# MCP41010.net
KiCad netlist of a schematic drawn in EasyEDA Pro
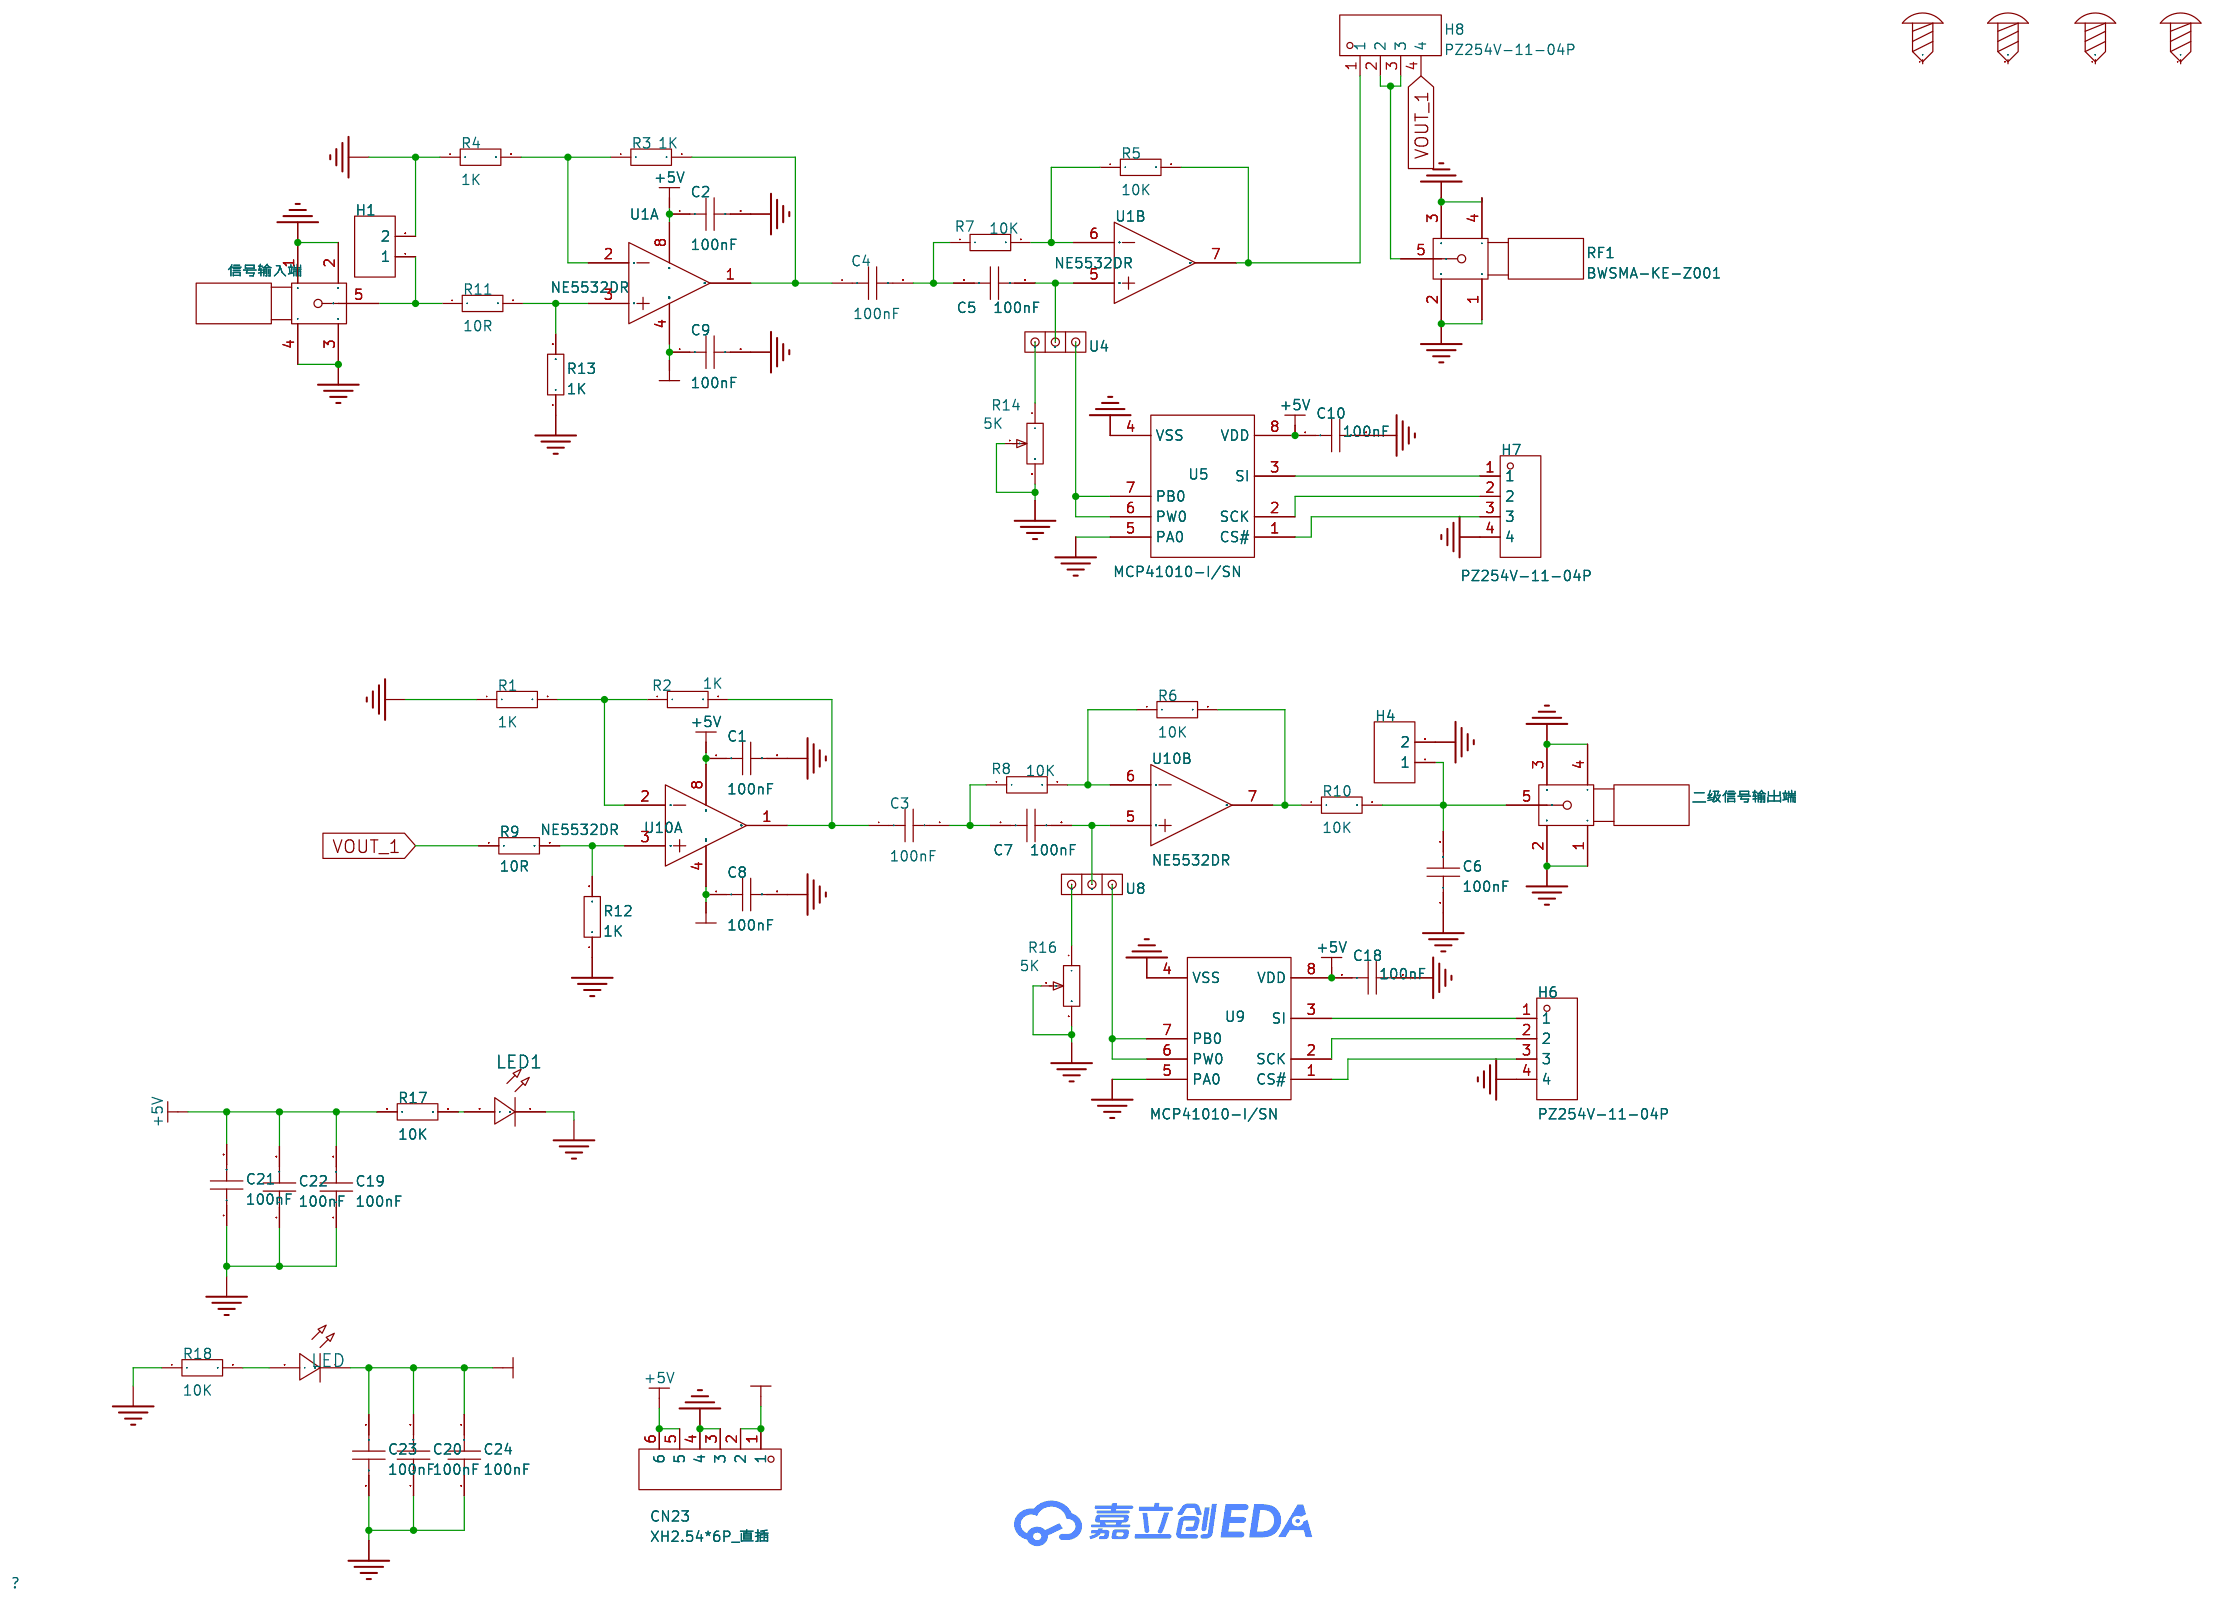
[diagram p0: schematic sheet]

(export (version "E")
  (design (tool "Eeschema 10.0.6"))
  (components
    (comp (ref "C1")
      (value "100nF")
      (footprint "easyedapro:C0805")
      (libsource (lib "easyedapro") (part "CapAcitance"))
    )
    (comp (ref "C2")
      (value "100nF")
      (footprint "easyedapro:C0805")
      (libsource (lib "easyedapro") (part "CapAcitance"))
    )
    (comp (ref "C3")
      (value "100nF")
      (footprint "easyedapro:C0805")
      (libsource (lib "easyedapro") (part "CapAcitance"))
    )
    (comp (ref "C4")
      (value "100nF")
      (footprint "easyedapro:C0805")
      (libsource (lib "easyedapro") (part "CapAcitance"))
    )
    (comp (ref "C5")
      (value "100nF")
      (footprint "easyedapro:C0805")
      (libsource (lib "easyedapro") (part "CapAcitance"))
    )
    (comp (ref "C6")
      (value "100nF")
      (footprint "easyedapro:C0805")
      (libsource (lib "easyedapro") (part "CapAcitance"))
    )
    (comp (ref "C7")
      (value "100nF")
      (footprint "easyedapro:C0805")
      (libsource (lib "easyedapro") (part "CapAcitance"))
    )
    (comp (ref "C8")
      (value "100nF")
      (footprint "easyedapro:C0805")
      (libsource (lib "easyedapro") (part "CapAcitance"))
    )
    (comp (ref "C9")
      (value "100nF")
      (footprint "easyedapro:C0805")
      (libsource (lib "easyedapro") (part "CapAcitance"))
    )
    (comp (ref "C10")
      (value "100nF")
      (footprint "easyedapro:C0805")
      (libsource (lib "easyedapro") (part "CapAcitance"))
    )
    (comp (ref "C18")
      (value "100nF")
      (footprint "easyedapro:C0805")
      (libsource (lib "easyedapro") (part "CapAcitance"))
    )
    (comp (ref "C19")
      (value "100nF")
      (footprint "easyedapro:C0805")
      (libsource (lib "easyedapro") (part "CapAcitance"))
    )
    (comp (ref "C20")
      (value "100nF")
      (footprint "easyedapro:C0805")
      (libsource (lib "easyedapro") (part "CapAcitance"))
    )
    (comp (ref "C21")
      (value "100nF")
      (footprint "easyedapro:C0805")
      (libsource (lib "easyedapro") (part "CapAcitance"))
    )
    (comp (ref "C22")
      (value "100nF")
      (footprint "easyedapro:C0805")
      (libsource (lib "easyedapro") (part "CapAcitance"))
    )
    (comp (ref "C23")
      (value "100nF")
      (footprint "easyedapro:C0805")
      (libsource (lib "easyedapro") (part "CapAcitance"))
    )
    (comp (ref "C24")
      (value "100nF")
      (footprint "easyedapro:C0805")
      (libsource (lib "easyedapro") (part "CapAcitance"))
    )
    (comp (ref "CN23")
      (value "XH2.54*6P_直插")
      (footprint "easyedapro:CONN-TH_XH2.54-6P")
      (libsource (lib "easyedapro") (part "XH2.54*6P_直插"))
    )
    (comp (ref "H1")
      (value "~")
      (footprint "easyedapro:HDR-TH_2P-P2.54-V-F")
      (libsource (lib "easyedapro") (part "Header-Female-2.54_1x2"))
    )
    (comp (ref "H4")
      (value "~")
      (footprint "easyedapro:HDR-TH_2P-P2.54-V-F")
      (libsource (lib "easyedapro") (part "Header-Female-2.54_1x2"))
    )
    (comp (ref "H6")
      (value "PZ254V-11-04P")
      (footprint "easyedapro:HDR-TH_4P-P2.54-V-M")
      (fields (field (name "Manufacturer") "XFCN(兴飞)"))
      (libsource (lib "easyedapro") (part "PZ254V-11-04P_C2691448"))
    )
    (comp (ref "H7")
      (value "PZ254V-11-04P")
      (footprint "easyedapro:HDR-TH_4P-P2.54-V-M")
      (fields (field (name "Manufacturer") "XFCN(兴飞)"))
      (libsource (lib "easyedapro") (part "PZ254V-11-04P_C2691448"))
    )
    (comp (ref "H8")
      (value "PZ254V-11-04P")
      (footprint "easyedapro:HDR-TH_4P-P2.54-V-M")
      (fields (field (name "Manufacturer") "XFCN(兴飞)"))
      (libsource (lib "easyedapro") (part "PZ254V-11-04P_C2691448"))
    )
    (comp (ref "LED")
      (value "~")
      (footprint "easyedapro:LED_0805")
      (libsource (lib "easyedapro") (part "LED_R"))
    )
    (comp (ref "LED1")
      (value "~")
      (footprint "easyedapro:LED_0805")
      (libsource (lib "easyedapro") (part "LED_R"))
    )
    (comp (ref "R1") (value "1K") (footprint "easyedapro:R0805") (libsource (lib "easyedapro") (part "电阻")))
    (comp (ref "R2") (value "1K") (footprint "easyedapro:R0805") (libsource (lib "easyedapro") (part "电阻")))
    (comp (ref "R3") (value "1K") (footprint "easyedapro:R0805") (libsource (lib "easyedapro") (part "电阻")))
    (comp (ref "R4") (value "1K") (footprint "easyedapro:R0805") (libsource (lib "easyedapro") (part "电阻")))
    (comp (ref "R5") (value "10K") (footprint "easyedapro:R0805") (libsource (lib "easyedapro") (part "电阻")))
    (comp (ref "R6") (value "10K") (footprint "easyedapro:R0805") (libsource (lib "easyedapro") (part "电阻")))
    (comp (ref "R7") (value "10K") (footprint "easyedapro:R0805") (libsource (lib "easyedapro") (part "电阻")))
    (comp (ref "R8") (value "10K") (footprint "easyedapro:R0805") (libsource (lib "easyedapro") (part "电阻")))
    (comp (ref "R9") (value "10R") (footprint "easyedapro:R0805") (libsource (lib "easyedapro") (part "电阻")))
    (comp (ref "R10") (value "10K") (footprint "easyedapro:R0805") (libsource (lib "easyedapro") (part "电阻")))
    (comp (ref "R11") (value "10R") (footprint "easyedapro:R0805") (libsource (lib "easyedapro") (part "电阻")))
    (comp (ref "R12") (value "1K") (footprint "easyedapro:R0805") (libsource (lib "easyedapro") (part "电阻")))
    (comp (ref "R13") (value "1K") (footprint "easyedapro:R0805") (libsource (lib "easyedapro") (part "电阻")))
    (comp (ref "R14")
      (value "5K")
      (footprint "easyedapro:R_3296")
      (libsource (lib "easyedapro") (part "R_3296"))
    )
    (comp (ref "R16")
      (value "5K")
      (footprint "easyedapro:R_3296")
      (libsource (lib "easyedapro") (part "R_3296"))
    )
    (comp (ref "R17") (value "10K") (footprint "easyedapro:R0805") (libsource (lib "easyedapro") (part "电阻")))
    (comp (ref "R18") (value "10K") (footprint "easyedapro:R0805") (libsource (lib "easyedapro") (part "电阻")))
    (comp (ref "RF1")
      (value "BWSMA-KE-Z001")
      (footprint "easyedapro:SMA-TH_BWSMA-KE-Z001")
      (fields (field (name "Manufacturer") "BAT WIRELESS(蝙蝠无线)"))
      (libsource (lib "easyedapro") (part "BWSMA-KE-Z001"))
    )
    (comp (ref "SCREW1")
      (value "~")
      (footprint "easyedapro:M3螺丝")
      (libsource (lib "easyedapro") (part "螺丝孔"))
    )
    (comp (ref "SCREW2")
      (value "~")
      (footprint "easyedapro:M3螺丝")
      (libsource (lib "easyedapro") (part "螺丝孔"))
    )
    (comp (ref "SCREW3")
      (value "~")
      (footprint "easyedapro:M3螺丝")
      (libsource (lib "easyedapro") (part "螺丝孔"))
    )
    (comp (ref "SCREW4")
      (value "~")
      (footprint "easyedapro:M3螺丝")
      (libsource (lib "easyedapro") (part "螺丝孔"))
    )
    (comp (ref "U1")
      (value "NE5532DR")
      (footprint "easyedapro:SOIC-8_L4.9-W3.9-P1.27-LS6.0-BL")
      (description "放大器数:双路;增益带宽积(GBP):10MHz;输入偏置电流(Ib):200nA;压摆率(SR):9V/us;带宽(-3db):-;")
      (fields (field (name "Manufacturer") "TI(德州仪器)"))
      (libsource (lib "easyedapro") (part "NE5532DR"))
    )
    (comp (ref "U4") (value "~") (footprint "easyedapro:1*3跳线") (libsource (lib "easyedapro") (part "1*3跳线")))
    (comp (ref "U5")
      (value "MCP41010-I/SN")
      (footprint "easyedapro:SOIC-8_L4.9-W3.9-P1.27-LS6.0-BL")
      (description "电阻值(欧姆):10kΩ;精度:±20%;供电电压:2.7V~5.5V;接口类型:SPI;")
      (fields (field (name "Manufacturer") "MICROCHIP(美国微芯)"))
      (libsource (lib "easyedapro") (part "MCP41010-I/SN"))
    )
    (comp (ref "U8") (value "~") (footprint "easyedapro:1*3跳线") (libsource (lib "easyedapro") (part "1*3跳线")))
    (comp (ref "U9")
      (value "MCP41010-I/SN")
      (footprint "easyedapro:SOIC-8_L4.9-W3.9-P1.27-LS6.0-BL")
      (description "电阻值(欧姆):10kΩ;精度:±20%;供电电压:2.7V~5.5V;接口类型:SPI;")
      (fields (field (name "Manufacturer") "MICROCHIP(美国微芯)"))
      (libsource (lib "easyedapro") (part "MCP41010-I/SN"))
    )
    (comp (ref "U10")
      (value "NE5532DR")
      (footprint "easyedapro:SOIC-8_L4.9-W3.9-P1.27-LS6.0-BL")
      (description "放大器数:双路;增益带宽积(GBP):10MHz;输入偏置电流(Ib):200nA;压摆率(SR):9V/us;带宽(-3db):-;")
      (fields (field (name "Manufacturer") "TI(德州仪器)"))
      (libsource (lib "easyedapro") (part "NE5532DR"))
    )
    (comp (ref "二级信号输出端")
      (value "~")
      (footprint "easyedapro:SMA")
      (libsource (lib "easyedapro") (part "SMA"))
    )
    (comp (ref "信号输入端") (value "~") (footprint "easyedapro:SMA") (libsource (lib "easyedapro") (part "SMA")))
  )
  (nets
    (net (code "1") (name "+5V") (class "Default")
      (node (ref "C1") (pin "1") (pinfunction "1_1") (pintype "input"))
      (node (ref "C10") (pin "1") (pinfunction "1_1") (pintype "input"))
      (node (ref "C18") (pin "1") (pinfunction "1_1") (pintype "input"))
      (node (ref "C19") (pin "2") (pinfunction "2_2") (pintype "input"))
      (node (ref "C2") (pin "1") (pinfunction "1_1") (pintype "input"))
      (node (ref "C21") (pin "2") (pinfunction "2_2") (pintype "input"))
      (node (ref "C22") (pin "2") (pinfunction "2_2") (pintype "input"))
      (node (ref "CN23") (pin "5") (pinfunction "5_5") (pintype "input"))
      (node (ref "CN23") (pin "6") (pinfunction "6_6") (pintype "input"))
      (node (ref "R17") (pin "1") (pinfunction "1_1") (pintype "input"))
      (node (ref "U1") (pin "8") (pinfunction "VCC+_8") (pintype "unspecified"))
      (node (ref "U10") (pin "8") (pinfunction "VCC+_8") (pintype "unspecified"))
      (node (ref "U5") (pin "8") (pinfunction "VDD_8") (pintype "unspecified"))
      (node (ref "U9") (pin "8") (pinfunction "VDD_8") (pintype "unspecified"))
    )
    (net (code "2") (name "-5V") (class "Default")
      (node (ref "C20") (pin "2") (pinfunction "2_2") (pintype "input"))
      (node (ref "C23") (pin "1") (pinfunction "1_1") (pintype "input"))
      (node (ref "C24") (pin "1") (pinfunction "1_1") (pintype "input"))
      (node (ref "C8") (pin "1") (pinfunction "1_1") (pintype "input"))
      (node (ref "C9") (pin "1") (pinfunction "1_1") (pintype "input"))
      (node (ref "CN23") (pin "1") (pinfunction "1_1") (pintype "input"))
      (node (ref "CN23") (pin "2") (pinfunction "2_2") (pintype "input"))
      (node (ref "LED") (pin "1") (pinfunction "C_1") (pintype "input"))
      (node (ref "U1") (pin "4") (pinfunction "VCC-/GND_4") (pintype "unspecified"))
      (node (ref "U10") (pin "4") (pinfunction "VCC-/GND_4") (pintype "unspecified"))
    )
    (net (code "3") (name "GND") (class "Default")
      (node (ref "C1") (pin "2") (pinfunction "2_2") (pintype "input"))
      (node (ref "C10") (pin "2") (pinfunction "2_2") (pintype "input"))
      (node (ref "C18") (pin "2") (pinfunction "2_2") (pintype "input"))
      (node (ref "C19") (pin "1") (pinfunction "1_1") (pintype "input"))
      (node (ref "C2") (pin "2") (pinfunction "2_2") (pintype "input"))
      (node (ref "C20") (pin "1") (pinfunction "1_1") (pintype "input"))
      (node (ref "C21") (pin "1") (pinfunction "1_1") (pintype "input"))
      (node (ref "C22") (pin "1") (pinfunction "1_1") (pintype "input"))
      (node (ref "C23") (pin "2") (pinfunction "2_2") (pintype "input"))
      (node (ref "C24") (pin "2") (pinfunction "2_2") (pintype "input"))
      (node (ref "C6") (pin "1") (pinfunction "1_1") (pintype "input"))
      (node (ref "C8") (pin "2") (pinfunction "2_2") (pintype "input"))
      (node (ref "C9") (pin "2") (pinfunction "2_2") (pintype "input"))
      (node (ref "CN23") (pin "3") (pinfunction "3_3") (pintype "input"))
      (node (ref "CN23") (pin "4") (pinfunction "4_4") (pintype "input"))
      (node (ref "H1") (pin "2") (pinfunction "2_2") (pintype "input"))
      (node (ref "H4") (pin "2") (pinfunction "2_2") (pintype "input"))
      (node (ref "H6") (pin "4") (pinfunction "4_4") (pintype "unspecified"))
      (node (ref "H7") (pin "4") (pinfunction "4_4") (pintype "unspecified"))
      (node (ref "LED1") (pin "1") (pinfunction "C_1") (pintype "input"))
      (node (ref "R1") (pin "1") (pinfunction "1_1") (pintype "input"))
      (node (ref "R12") (pin "1") (pinfunction "1_1") (pintype "input"))
      (node (ref "R13") (pin "1") (pinfunction "1_1") (pintype "input"))
      (node (ref "R14") (pin "2") (pinfunction "2_2") (pintype "input"))
      (node (ref "R14") (pin "3") (pinfunction "3_3") (pintype "input"))
      (node (ref "R16") (pin "2") (pinfunction "2_2") (pintype "input"))
      (node (ref "R16") (pin "3") (pinfunction "3_3") (pintype "input"))
      (node (ref "R18") (pin "1") (pinfunction "1_1") (pintype "input"))
      (node (ref "R4") (pin "1") (pinfunction "1_1") (pintype "input"))
      (node (ref "RF1") (pin "1") (pinfunction "1_1") (pintype "unspecified"))
      (node (ref "RF1") (pin "2") (pinfunction "2_2") (pintype "unspecified"))
      (node (ref "RF1") (pin "3") (pinfunction "3_3") (pintype "unspecified"))
      (node (ref "RF1") (pin "4") (pinfunction "4_4") (pintype "unspecified"))
      (node (ref "U5") (pin "4") (pinfunction "VSS_4") (pintype "unspecified"))
      (node (ref "U5") (pin "5") (pinfunction "PA0_5") (pintype "unspecified"))
      (node (ref "U9") (pin "4") (pinfunction "VSS_4") (pintype "unspecified"))
      (node (ref "U9") (pin "5") (pinfunction "PA0_5") (pintype "unspecified"))
      (node (ref "二级信号输出端") (pin "1") (pinfunction "1_1") (pintype "input"))
      (node (ref "二级信号输出端") (pin "2") (pinfunction "2_2") (pintype "input"))
      (node (ref "二级信号输出端") (pin "3") (pinfunction "3_3") (pintype "input"))
      (node (ref "二级信号输出端") (pin "4") (pinfunction "4_4") (pintype "input"))
      (node (ref "信号输入端") (pin "1") (pinfunction "1_1") (pintype "input"))
      (node (ref "信号输入端") (pin "2") (pinfunction "2_2") (pintype "input"))
      (node (ref "信号输入端") (pin "3") (pinfunction "3_3") (pintype "input"))
      (node (ref "信号输入端") (pin "4") (pinfunction "4_4") (pintype "input"))
    )
    (net (code "4") (name "Net-(C3-Pad2)") (class "Default")
      (node (ref "C3") (pin "2") (pinfunction "2_2") (pintype "input"))
      (node (ref "C7") (pin "1") (pinfunction "1_1") (pintype "input"))
      (node (ref "R8") (pin "1") (pinfunction "1_1") (pintype "input"))
    )
    (net (code "5") (name "Net-(C4-Pad2)") (class "Default")
      (node (ref "C4") (pin "2") (pinfunction "2_2") (pintype "input"))
      (node (ref "C5") (pin "1") (pinfunction "1_1") (pintype "input"))
      (node (ref "R7") (pin "1") (pinfunction "1_1") (pintype "input"))
    )
    (net (code "6") (name "Net-(C6-Pad2)") (class "Default")
      (node (ref "C6") (pin "2") (pinfunction "2_2") (pintype "input"))
      (node (ref "H4") (pin "1") (pinfunction "1_1") (pintype "input"))
      (node (ref "R10") (pin "2") (pinfunction "2_2") (pintype "input"))
      (node (ref "二级信号输出端") (pin "5") (pinfunction "5_5") (pintype "input"))
    )
    (net (code "7") (name "Net-(H1-Pad1)") (class "Default")
      (node (ref "H1") (pin "1") (pinfunction "1_1") (pintype "input"))
      (node (ref "R11") (pin "1") (pinfunction "1_1") (pintype "input"))
      (node (ref "信号输入端") (pin "5") (pinfunction "5_5") (pintype "input"))
    )
    (net (code "8") (name "Net-(H8-Pad2)") (class "Default")
      (node (ref "H8") (pin "2") (pinfunction "2_2") (pintype "unspecified"))
      (node (ref "H8") (pin "3") (pinfunction "3_3") (pintype "unspecified"))
      (node (ref "RF1") (pin "5") (pinfunction "5_5") (pintype "unspecified"))
    )
    (net (code "9") (name "Net-(LED-A)") (class "Default")
      (node (ref "LED") (pin "2") (pinfunction "A_2") (pintype "input"))
      (node (ref "R18") (pin "2") (pinfunction "2_2") (pintype "input"))
    )
    (net (code "10") (name "Net-(LED1-A)") (class "Default")
      (node (ref "LED1") (pin "2") (pinfunction "A_2") (pintype "input"))
      (node (ref "R17") (pin "2") (pinfunction "2_2") (pintype "input"))
    )
    (net (code "11") (name "Net-(R14-Pad1)") (class "Default")
      (node (ref "R14") (pin "1") (pinfunction "1_1") (pintype "input"))
      (node (ref "U4") (pin "3") (pinfunction "3_3") (pintype "input"))
    )
    (net (code "12") (name "Net-(R16-Pad1)") (class "Default")
      (node (ref "R16") (pin "1") (pinfunction "1_1") (pintype "input"))
      (node (ref "U8") (pin "3") (pinfunction "3_3") (pintype "input"))
    )
    (net (code "13") (name "Net-(U1A-IN1+)") (class "Default")
      (node (ref "R11") (pin "2") (pinfunction "2_2") (pintype "input"))
      (node (ref "R13") (pin "2") (pinfunction "2_2") (pintype "input"))
      (node (ref "U1") (pin "3") (pinfunction "IN1+_3") (pintype "unspecified"))
    )
    (net (code "14") (name "Net-(U1A-IN1-)") (class "Default")
      (node (ref "R3") (pin "1") (pinfunction "1_1") (pintype "input"))
      (node (ref "R4") (pin "2") (pinfunction "2_2") (pintype "input"))
      (node (ref "U1") (pin "2") (pinfunction "IN1-_2") (pintype "unspecified"))
    )
    (net (code "15") (name "Net-(U1A-OUT1)") (class "Default")
      (node (ref "C4") (pin "1") (pinfunction "1_1") (pintype "input"))
      (node (ref "R3") (pin "2") (pinfunction "2_2") (pintype "input"))
      (node (ref "U1") (pin "1") (pinfunction "OUT1_1") (pintype "output"))
    )
    (net (code "16") (name "Net-(U1B-IN2+)") (class "Default")
      (node (ref "C5") (pin "2") (pinfunction "2_2") (pintype "input"))
      (node (ref "U1") (pin "5") (pinfunction "IN2+_5") (pintype "unspecified"))
      (node (ref "U4") (pin "2") (pinfunction "2_2") (pintype "input"))
    )
    (net (code "17") (name "Net-(U1B-IN2-)") (class "Default")
      (node (ref "R5") (pin "1") (pinfunction "1_1") (pintype "input"))
      (node (ref "R7") (pin "2") (pinfunction "2_2") (pintype "input"))
      (node (ref "U1") (pin "6") (pinfunction "IN2-_6") (pintype "unspecified"))
    )
    (net (code "18") (name "Net-(U1B-OUT2)") (class "Default")
      (node (ref "H8") (pin "1") (pinfunction "1_1") (pintype "unspecified"))
      (node (ref "R5") (pin "2") (pinfunction "2_2") (pintype "input"))
      (node (ref "U1") (pin "7") (pinfunction "OUT2_7") (pintype "output"))
    )
    (net (code "19") (name "Net-(U5-CS#)") (class "Default")
      (node (ref "H7") (pin "3") (pinfunction "3_3") (pintype "unspecified"))
      (node (ref "U5") (pin "1") (pinfunction "CS#_1") (pintype "unspecified"))
    )
    (net (code "20") (name "Net-(U5-PB0)") (class "Default")
      (node (ref "U4") (pin "1") (pinfunction "1_1") (pintype "input"))
      (node (ref "U5") (pin "6") (pinfunction "PW0_6") (pintype "unspecified"))
      (node (ref "U5") (pin "7") (pinfunction "PB0_7") (pintype "unspecified"))
    )
    (net (code "21") (name "Net-(U5-SCK)") (class "Default")
      (node (ref "H7") (pin "2") (pinfunction "2_2") (pintype "unspecified"))
      (node (ref "U5") (pin "2") (pinfunction "SCK_2") (pintype "unspecified"))
    )
    (net (code "22") (name "Net-(U5-SI)") (class "Default")
      (node (ref "H7") (pin "1") (pinfunction "1_1") (pintype "unspecified"))
      (node (ref "U5") (pin "3") (pinfunction "SI_3") (pintype "unspecified"))
    )
    (net (code "23") (name "Net-(U9-CS#)") (class "Default")
      (node (ref "H6") (pin "3") (pinfunction "3_3") (pintype "unspecified"))
      (node (ref "U9") (pin "1") (pinfunction "CS#_1") (pintype "unspecified"))
    )
    (net (code "24") (name "Net-(U9-PB0)") (class "Default")
      (node (ref "U8") (pin "1") (pinfunction "1_1") (pintype "input"))
      (node (ref "U9") (pin "6") (pinfunction "PW0_6") (pintype "unspecified"))
      (node (ref "U9") (pin "7") (pinfunction "PB0_7") (pintype "unspecified"))
    )
    (net (code "25") (name "Net-(U9-SCK)") (class "Default")
      (node (ref "H6") (pin "2") (pinfunction "2_2") (pintype "unspecified"))
      (node (ref "U9") (pin "2") (pinfunction "SCK_2") (pintype "unspecified"))
    )
    (net (code "26") (name "Net-(U9-SI)") (class "Default")
      (node (ref "H6") (pin "1") (pinfunction "1_1") (pintype "unspecified"))
      (node (ref "U9") (pin "3") (pinfunction "SI_3") (pintype "unspecified"))
    )
    (net (code "27") (name "Net-(U10A-IN1+)") (class "Default")
      (node (ref "R12") (pin "2") (pinfunction "2_2") (pintype "input"))
      (node (ref "R9") (pin "2") (pinfunction "2_2") (pintype "input"))
      (node (ref "U10") (pin "3") (pinfunction "IN1+_3") (pintype "unspecified"))
    )
    (net (code "28") (name "Net-(U10A-IN1-)") (class "Default")
      (node (ref "R1") (pin "2") (pinfunction "2_2") (pintype "input"))
      (node (ref "R2") (pin "1") (pinfunction "1_1") (pintype "input"))
      (node (ref "U10") (pin "2") (pinfunction "IN1-_2") (pintype "unspecified"))
    )
    (net (code "29") (name "Net-(U10A-OUT1)") (class "Default")
      (node (ref "C3") (pin "1") (pinfunction "1_1") (pintype "input"))
      (node (ref "R2") (pin "2") (pinfunction "2_2") (pintype "input"))
      (node (ref "U10") (pin "1") (pinfunction "OUT1_1") (pintype "output"))
    )
    (net (code "30") (name "Net-(U10B-IN2+)") (class "Default")
      (node (ref "C7") (pin "2") (pinfunction "2_2") (pintype "input"))
      (node (ref "U10") (pin "5") (pinfunction "IN2+_5") (pintype "unspecified"))
      (node (ref "U8") (pin "2") (pinfunction "2_2") (pintype "input"))
    )
    (net (code "31") (name "Net-(U10B-IN2-)") (class "Default")
      (node (ref "R6") (pin "1") (pinfunction "1_1") (pintype "input"))
      (node (ref "R8") (pin "2") (pinfunction "2_2") (pintype "input"))
      (node (ref "U10") (pin "6") (pinfunction "IN2-_6") (pintype "unspecified"))
    )
    (net (code "32") (name "Net-(U10B-OUT2)") (class "Default")
      (node (ref "R10") (pin "1") (pinfunction "1_1") (pintype "input"))
      (node (ref "R6") (pin "2") (pinfunction "2_2") (pintype "input"))
      (node (ref "U10") (pin "7") (pinfunction "OUT2_7") (pintype "output"))
    )
    (net (code "33") (name "VOUT_1") (class "Default")
      (node (ref "H8") (pin "4") (pinfunction "4_4") (pintype "unspecified"))
      (node (ref "R9") (pin "1") (pinfunction "1_1") (pintype "input"))
    )
    (net (code "34") (name "unconnected-(SCREW1-Pad1)") (class "Default")
      (node (ref "SCREW1") (pin "1") (pinfunction "1_1") (pintype "input"))
    )
    (net (code "35") (name "unconnected-(SCREW2-Pad1)") (class "Default")
      (node (ref "SCREW2") (pin "1") (pinfunction "1_1") (pintype "input"))
    )
    (net (code "36") (name "unconnected-(SCREW3-Pad1)") (class "Default")
      (node (ref "SCREW3") (pin "1") (pinfunction "1_1") (pintype "input"))
    )
    (net (code "37") (name "unconnected-(SCREW4-Pad1)") (class "Default")
      (node (ref "SCREW4") (pin "1") (pinfunction "1_1") (pintype "input"))
    )
  )
)
